# SMC-DCc10.net
KiCad netlist of a schematic drawn in EAGLE
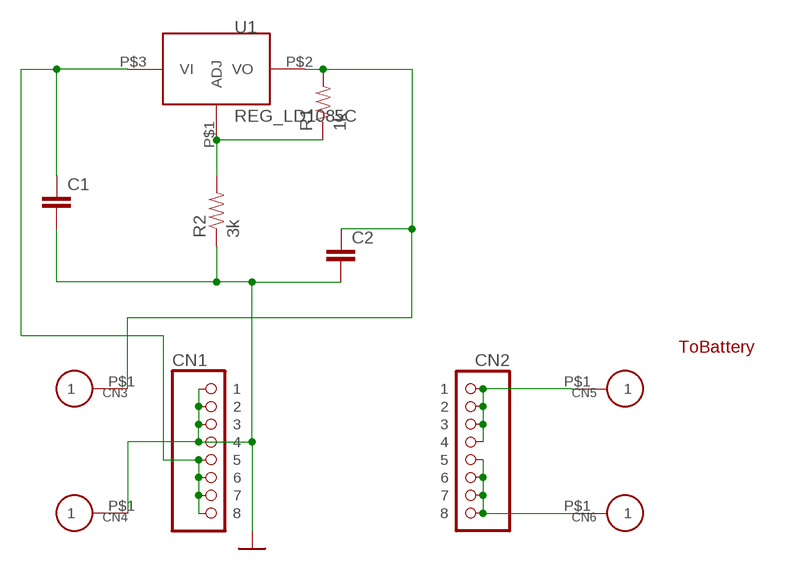
[diagram p0: schematic, sheet 1]

(export (version "E")
  (design (tool "Eeschema 10.0.6"))
  (components
    (comp (ref "C1")
      (value "CAP0603")
      (footprint "eagle-import:0603")
      (libsource (lib "eagle-import") (part "CAP0603"))
    )
    (comp (ref "C2")
      (value "CAP1206")
      (footprint "eagle-import:1206")
      (libsource (lib "eagle-import") (part "CAP1206"))
    )
    (comp (ref "CN1")
      (value "CON_PINHD-1X8FPC05")
      (footprint "eagle-import:CON_8P_FPC05MM")
      (libsource (lib "eagle-import") (part "CON_PINHD-1X8FPC05"))
    )
    (comp (ref "CN2")
      (value "CON_PINHD-1X8FPC05")
      (footprint "eagle-import:CON_8P_FPC05MM")
      (libsource (lib "eagle-import") (part "CON_PINHD-1X8FPC05"))
    )
    (comp (ref "CN3")
      (value "CON_P01SMD1MM")
      (footprint "eagle-import:PAD_SMD1MM")
      (libsource (lib "eagle-import") (part "CON_P01SMD1MM"))
    )
    (comp (ref "CN4")
      (value "CON_P01SMD1MM")
      (footprint "eagle-import:PAD_SMD1MM")
      (libsource (lib "eagle-import") (part "CON_P01SMD1MM"))
    )
    (comp (ref "CN5")
      (value "CON_P01SMD1MM")
      (footprint "eagle-import:PAD_SMD1MM")
      (libsource (lib "eagle-import") (part "CON_P01SMD1MM"))
    )
    (comp (ref "CN6")
      (value "CON_P01SMD1MM")
      (footprint "eagle-import:PAD_SMD1MM")
      (libsource (lib "eagle-import") (part "CON_P01SMD1MM"))
    )
    (comp (ref "R1")
      (value "1k")
      (footprint "eagle-import:0603")
      (libsource (lib "eagle-import") (part "RES0603"))
    )
    (comp (ref "R2")
      (value "3k")
      (footprint "eagle-import:0603")
      (libsource (lib "eagle-import") (part "RES0603"))
    )
    (comp (ref "U1")
      (value "REG_LD1085C")
      (footprint "eagle-import:TO-252-3")
      (libsource (lib "eagle-import") (part "REG_LD1085C"))
    )
  )
  (nets
    (net (code "1") (name "Net-(C2-1)") (class "Default")
      (node (ref "C2") (pin "P$1") (pinfunction "1_P$1") (pintype "passive"))
      (node (ref "CN3") (pin "P$1") (pinfunction "1_P$1") (pintype "bidirectional"))
      (node (ref "R1") (pin "2") (pinfunction "2_2") (pintype "passive"))
      (node (ref "U1") (pin "P$2") (pinfunction "VO_P$2") (pintype "bidirectional"))
    )
    (net (code "2") (name "Net-(CN1-5)") (class "Default")
      (node (ref "C1") (pin "1") (pinfunction "1_1") (pintype "passive"))
      (node (ref "CN1") (pin "P$5") (pinfunction "5_P$5") (pintype "passive"))
      (node (ref "CN1") (pin "P$6") (pinfunction "6_P$6") (pintype "passive"))
      (node (ref "CN1") (pin "P$7") (pinfunction "7_P$7") (pintype "passive"))
      (node (ref "CN1") (pin "P$8") (pinfunction "8_P$8") (pintype "passive"))
      (node (ref "U1") (pin "P$3") (pinfunction "VI_P$3") (pintype "bidirectional"))
    )
    (net (code "3") (name "Net-(CN2-1)") (class "Default")
      (node (ref "CN2") (pin "P$1") (pinfunction "1_P$1") (pintype "passive"))
      (node (ref "CN2") (pin "P$2") (pinfunction "2_P$2") (pintype "passive"))
      (node (ref "CN2") (pin "P$3") (pinfunction "3_P$3") (pintype "passive"))
      (node (ref "CN2") (pin "P$4") (pinfunction "4_P$4") (pintype "passive"))
      (node (ref "CN5") (pin "P$1") (pinfunction "1_P$1") (pintype "bidirectional"))
    )
    (net (code "4") (name "Net-(CN2-5)") (class "Default")
      (node (ref "CN2") (pin "P$5") (pinfunction "5_P$5") (pintype "passive"))
      (node (ref "CN2") (pin "P$6") (pinfunction "6_P$6") (pintype "passive"))
      (node (ref "CN2") (pin "P$7") (pinfunction "7_P$7") (pintype "passive"))
      (node (ref "CN2") (pin "P$8") (pinfunction "8_P$8") (pintype "passive"))
      (node (ref "CN6") (pin "P$1") (pinfunction "1_P$1") (pintype "bidirectional"))
    )
    (net (code "5") (name "Net-(U1-ADJ)") (class "Default")
      (node (ref "R1") (pin "1") (pinfunction "1_1") (pintype "passive"))
      (node (ref "R2") (pin "2") (pinfunction "2_2") (pintype "passive"))
      (node (ref "U1") (pin "P$1") (pinfunction "ADJ_P$1") (pintype "bidirectional"))
    )
    (net (code "6") (name "POW_GND") (class "Default")
      (node (ref "C1") (pin "2") (pinfunction "2_2") (pintype "passive"))
      (node (ref "C2") (pin "P$2") (pinfunction "2_P$2") (pintype "passive"))
      (node (ref "CN1") (pin "P$1") (pinfunction "1_P$1") (pintype "passive"))
      (node (ref "CN1") (pin "P$2") (pinfunction "2_P$2") (pintype "passive"))
      (node (ref "CN1") (pin "P$3") (pinfunction "3_P$3") (pintype "passive"))
      (node (ref "CN1") (pin "P$4") (pinfunction "4_P$4") (pintype "passive"))
      (node (ref "CN4") (pin "P$1") (pinfunction "1_P$1") (pintype "bidirectional"))
      (node (ref "R2") (pin "1") (pinfunction "1_1") (pintype "passive"))
    )
  )
)
